# ps.net
KiCad netlist of a schematic drawn in EAGLE
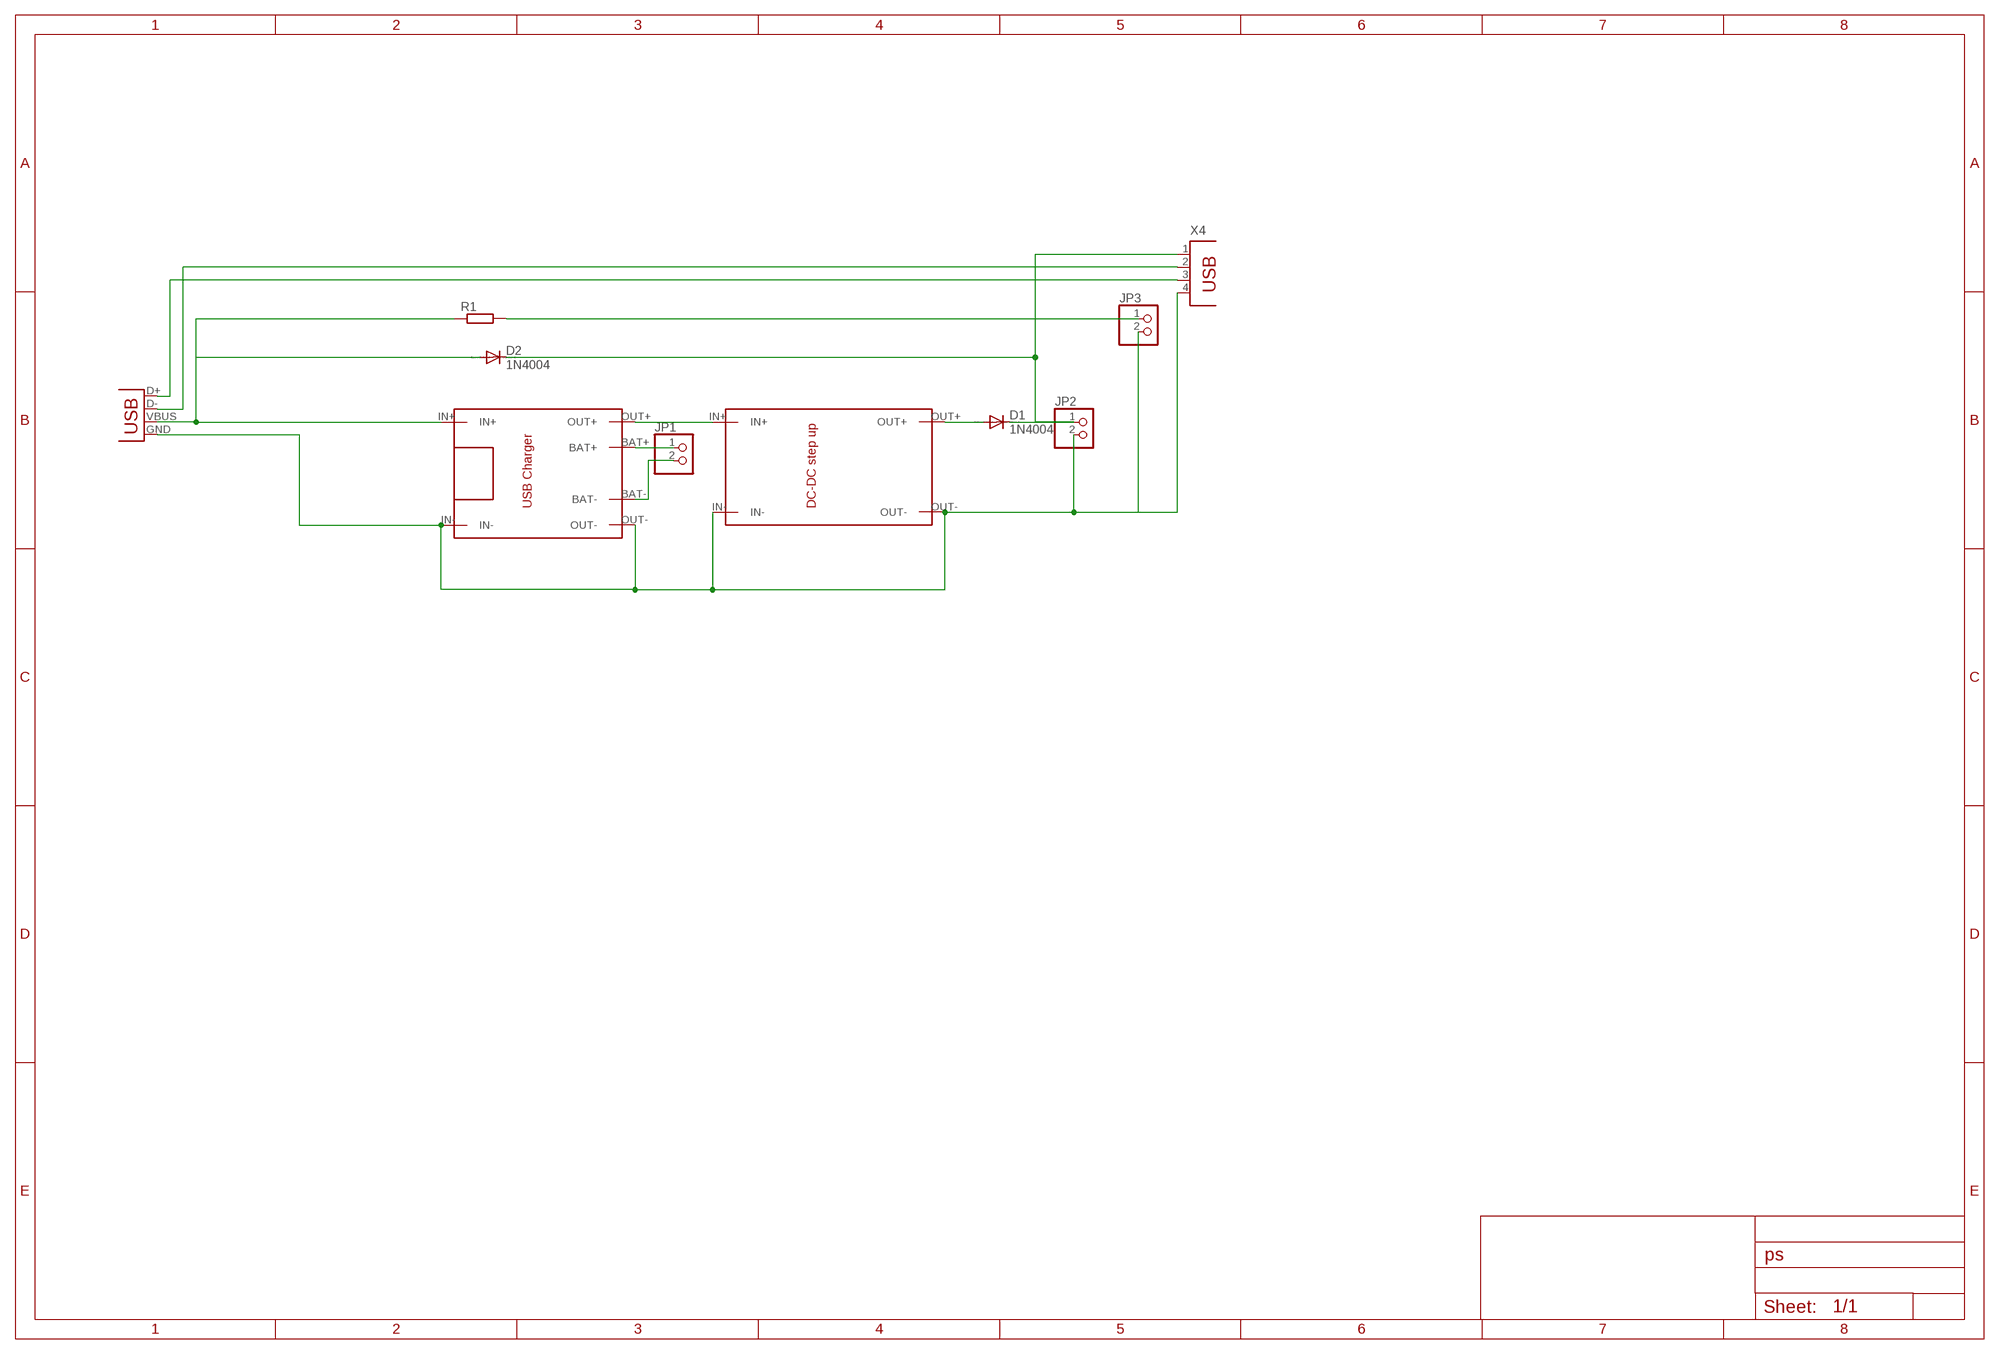
[diagram p0: schematic, sheet 1]

(export (version "E")
  (design (tool "Eeschema 10.0.6"))
  (components
    (comp (ref "D1")
      (value "1N4004")
      (footprint "eagle-import:DO41-10")
      (libsource (lib "eagle-import") (part "1N4004"))
    )
    (comp (ref "D2")
      (value "1N4004")
      (footprint "eagle-import:DO41-10")
      (libsource (lib "eagle-import") (part "1N4004"))
    )
    (comp (ref "JP1")
      (value "PINHD-1X2")
      (footprint "eagle-import:1X02")
      (libsource (lib "eagle-import") (part "PINHD-1X2"))
    )
    (comp (ref "JP2")
      (value "PINHD-1X2")
      (footprint "eagle-import:1X02")
      (libsource (lib "eagle-import") (part "PINHD-1X2"))
    )
    (comp (ref "JP3")
      (value "PINHD-1X2")
      (footprint "eagle-import:1X02")
      (libsource (lib "eagle-import") (part "PINHD-1X2"))
    )
    (comp (ref "R1")
      (value "R-EU_0204/7")
      (footprint "eagle-import:0204_7")
      (libsource (lib "eagle-import") (part "R-EU_0204/7"))
    )
    (comp (ref "U$1")
      (value "TP4056")
      (footprint "eagle-import:TP4056")
      (libsource (lib "eagle-import") (part "TP4056"))
    )
    (comp (ref "U$2")
      (value "DC-DC_STEPUP")
      (footprint "eagle-import:DC-DC_STEPUP")
      (libsource (lib "eagle-import") (part "DC-DC_STEPUP"))
    )
    (comp (ref "X3")
      (value "USBPTH")
      (footprint "eagle-import:USB-B-PTH")
      (libsource (lib "eagle-import") (part "USBPTH"))
    )
    (comp (ref "X4")
      (value "PN87520")
      (footprint "eagle-import:PN87520")
      (libsource (lib "eagle-import") (part "PN87520"))
    )
  )
  (nets
    (net (code "1") (name "Net-(D1-PadA)") (class "Default")
      (node (ref "D1") (pin "A") (pinfunction "A_A") (pintype "passive"))
      (node (ref "U$2") (pin "OUT+") (pinfunction "OUT+_OUT+") (pintype "bidirectional"))
    )
    (net (code "2") (name "Net-(D1-PadC)") (class "Default")
      (node (ref "D1") (pin "C") (pinfunction "C_C") (pintype "passive"))
      (node (ref "D2") (pin "C") (pinfunction "C_C") (pintype "passive"))
      (node (ref "JP2") (pin "1") (pinfunction "1_1") (pintype "passive"))
      (node (ref "X4") (pin "1") (pinfunction "1_1") (pintype "passive"))
    )
    (net (code "3") (name "Net-(D2-PadA)") (class "Default")
      (node (ref "D2") (pin "A") (pinfunction "A_A") (pintype "passive"))
      (node (ref "R1") (pin "1") (pinfunction "1_1") (pintype "passive"))
      (node (ref "U$1") (pin "IN+") (pinfunction "IN+_IN+") (pintype "bidirectional"))
      (node (ref "X3") (pin "VBUS") (pinfunction "VBUS_VBUS") (pintype "bidirectional"))
    )
    (net (code "4") (name "Net-(JP1-Pad1)") (class "Default")
      (node (ref "JP1") (pin "1") (pinfunction "1_1") (pintype "passive"))
      (node (ref "U$1") (pin "BAT+") (pinfunction "BAT+_BAT+") (pintype "bidirectional"))
    )
    (net (code "5") (name "Net-(JP1-Pad2)") (class "Default")
      (node (ref "JP1") (pin "2") (pinfunction "2_2") (pintype "passive"))
      (node (ref "U$1") (pin "BAT-") (pinfunction "BAT-_BAT-") (pintype "bidirectional"))
    )
    (net (code "6") (name "Net-(JP2-Pad2)") (class "Default")
      (node (ref "JP2") (pin "2") (pinfunction "2_2") (pintype "passive"))
      (node (ref "JP3") (pin "2") (pinfunction "2_2") (pintype "passive"))
      (node (ref "U$1") (pin "IN-") (pinfunction "IN-_IN-") (pintype "bidirectional"))
      (node (ref "U$1") (pin "OUT-") (pinfunction "OUT-_OUT-") (pintype "bidirectional"))
      (node (ref "U$2") (pin "IN-") (pinfunction "IN-_IN-") (pintype "bidirectional"))
      (node (ref "U$2") (pin "OUT-") (pinfunction "OUT-_OUT-") (pintype "bidirectional"))
      (node (ref "X3") (pin "GND") (pinfunction "GND_GND") (pintype "bidirectional"))
      (node (ref "X4") (pin "4") (pinfunction "4_4") (pintype "passive"))
    )
    (net (code "7") (name "Net-(JP3-Pad1)") (class "Default")
      (node (ref "JP3") (pin "1") (pinfunction "1_1") (pintype "passive"))
      (node (ref "R1") (pin "2") (pinfunction "2_2") (pintype "passive"))
    )
    (net (code "8") (name "Net-(U$1-PadOUT+)") (class "Default")
      (node (ref "U$1") (pin "OUT+") (pinfunction "OUT+_OUT+") (pintype "bidirectional"))
      (node (ref "U$2") (pin "IN+") (pinfunction "IN+_IN+") (pintype "bidirectional"))
    )
    (net (code "9") (name "Net-(X3-PadD+)") (class "Default")
      (node (ref "X3") (pin "D+") (pinfunction "D+_D+") (pintype "bidirectional"))
      (node (ref "X4") (pin "3") (pinfunction "3_3") (pintype "passive"))
    )
    (net (code "10") (name "Net-(X3-PadD-)") (class "Default")
      (node (ref "X3") (pin "D-") (pinfunction "D-_D-") (pintype "bidirectional"))
      (node (ref "X4") (pin "2") (pinfunction "2_2") (pintype "passive"))
    )
  )
)
